# ife19_Elec_TS_BrakePedal.net
KiCad netlist of a schematic drawn in Altium Designer
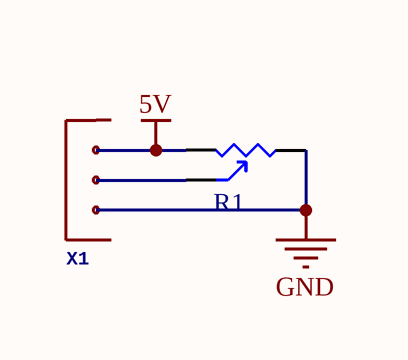
[diagram p0: ife19_Elec_TS_BrakePedal.SchDoc]

(export (version "E")
  (design (tool "Eeschema 10.0.6"))
  (components
    (comp (ref "R1")
      (value "POT_BEI9605")
      (footprint "POT_BEI9605")
      (libsource (lib "ife19_Elec_Library") (part "POT_BEI9605"))
    )
    (comp (ref "X1")
      (value "Molex 505575-03 3 Position 2.00mm pitch connector wire to board connector Datasheet")
      (footprint "505578-03")
      (fields (field (name "LIBRARYNAME") "MOLEX Micro-Lock"))
      (libsource (lib "ife19_Elec_Conn_Library") (part "POS3_ML505578-03"))
    )
  )
  (nets
    (net (code "1") (name "5V") (class "Default")
      (node (ref "R1") (pin "1") (pinfunction "1_1") (pintype "passive"))
      (node (ref "X1") (pin "3") (pinfunction "3_3") (pintype "passive"))
    )
    (net (code "2") (name "GND") (class "Default")
      (node (ref "R1") (pin "3") (pinfunction "3_3") (pintype "passive"))
      (node (ref "X1") (pin "1") (pinfunction "1_1") (pintype "passive"))
    )
    (net (code "3") (name "Net-(R1-Pad2)") (class "Default")
      (node (ref "R1") (pin "2") (pinfunction "2_2") (pintype "passive"))
      (node (ref "X1") (pin "2") (pinfunction "2_2") (pintype "passive"))
    )
  )
)
